# Qwiic_Ninja_Star.net
KiCad netlist of a schematic drawn in EAGLE
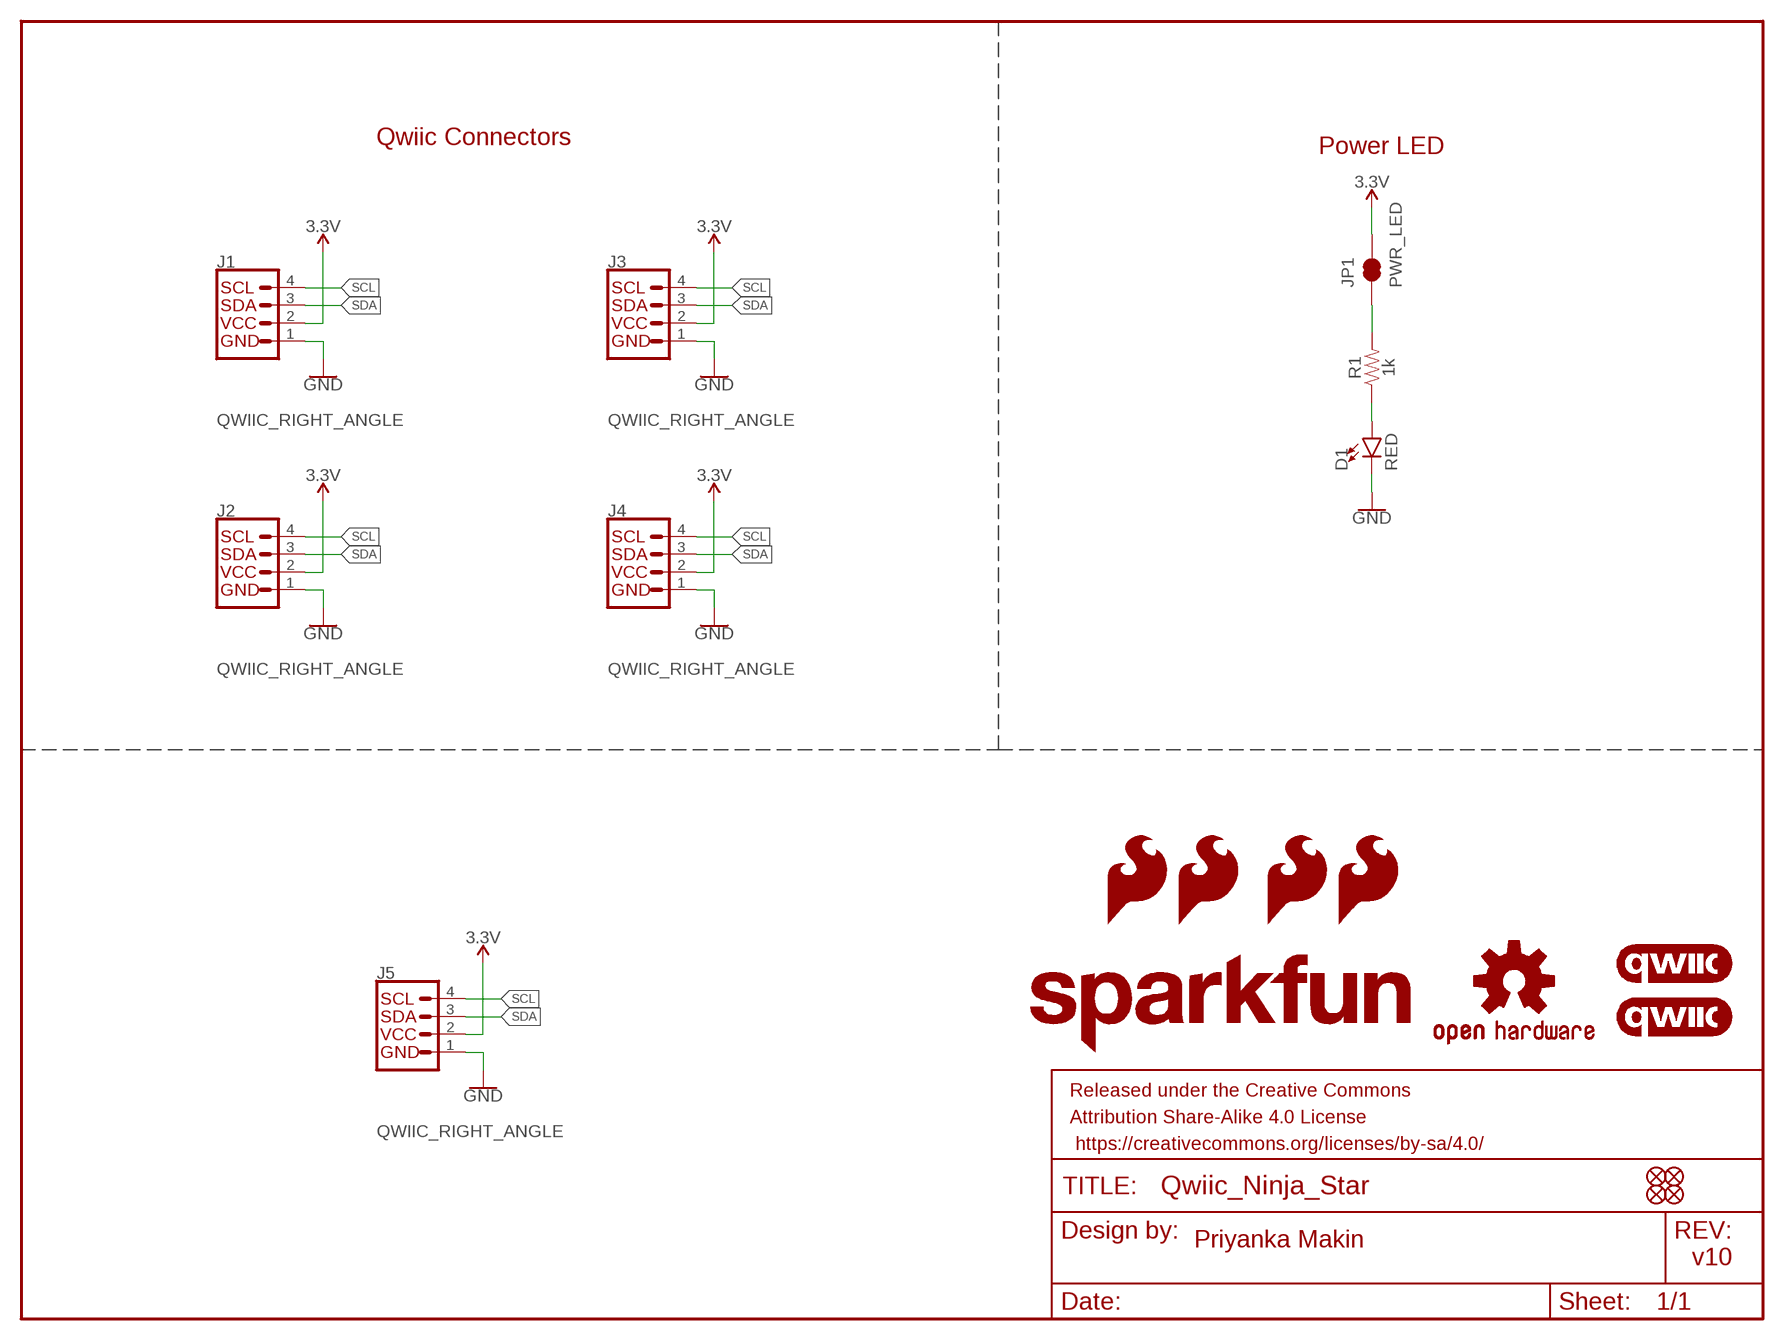
[diagram p0: schematic, sheet 1]

(export (version "E")
  (design (tool "Eeschema 10.0.6"))
  (components
    (comp (ref "D1")
      (value "RED")
      (footprint "eagle-import:LED-0603")
      (libsource (lib "eagle-import") (part "LED-RED0603"))
    )
    (comp (ref "FD1")
      (value "FIDUCIAL1X2")
      (footprint "eagle-import:FIDUCIAL-1X2")
      (libsource (lib "eagle-import") (part "FIDUCIAL1X2"))
    )
    (comp (ref "FD2")
      (value "FIDUCIAL1X2")
      (footprint "eagle-import:FIDUCIAL-1X2")
      (libsource (lib "eagle-import") (part "FIDUCIAL1X2"))
    )
    (comp (ref "FD3")
      (value "FIDUCIAL1X2")
      (footprint "eagle-import:FIDUCIAL-1X2")
      (libsource (lib "eagle-import") (part "FIDUCIAL1X2"))
    )
    (comp (ref "FD4")
      (value "FIDUCIAL1X2")
      (footprint "eagle-import:FIDUCIAL-1X2")
      (libsource (lib "eagle-import") (part "FIDUCIAL1X2"))
    )
    (comp (ref "FRAME1")
      (value "FRAME-LETTER")
      (footprint "eagle-import:CREATIVE_COMMONS")
      (libsource (lib "eagle-import") (part "FRAME-LETTER"))
    )
    (comp (ref "J1")
      (value "QWIIC_RIGHT_ANGLE")
      (footprint "eagle-import:JST04_1MM_RA")
      (libsource (lib "eagle-import") (part "QWIIC_CONNECTORJS-1MM"))
    )
    (comp (ref "J2")
      (value "QWIIC_RIGHT_ANGLE")
      (footprint "eagle-import:JST04_1MM_RA")
      (libsource (lib "eagle-import") (part "QWIIC_CONNECTORJS-1MM"))
    )
    (comp (ref "J3")
      (value "QWIIC_RIGHT_ANGLE")
      (footprint "eagle-import:JST04_1MM_RA")
      (libsource (lib "eagle-import") (part "QWIIC_CONNECTORJS-1MM"))
    )
    (comp (ref "J4")
      (value "QWIIC_RIGHT_ANGLE")
      (footprint "eagle-import:JST04_1MM_RA")
      (libsource (lib "eagle-import") (part "QWIIC_CONNECTORJS-1MM"))
    )
    (comp (ref "J5")
      (value "QWIIC_RIGHT_ANGLE")
      (footprint "eagle-import:JST04_1MM_RA")
      (libsource (lib "eagle-import") (part "QWIIC_CONNECTORJS-1MM"))
    )
    (comp (ref "JP1")
      (value "PWR_LED")
      (footprint "eagle-import:SMT-JUMPER_2_NC_TRACE_SILK")
      (libsource (lib "eagle-import") (part "JUMPER-SMT_2_NC_TRACE_SILK"))
    )
    (comp (ref "LOGO1")
      (value "QWIIC_LOGO_5MM")
      (footprint "eagle-import:QWIIC_5MM")
      (libsource (lib "eagle-import") (part "QWIIC_LOGO_5MM"))
    )
    (comp (ref "LOGO2")
      (value "QWIIC_LOGO_5MM")
      (footprint "eagle-import:QWIIC_5MM")
      (libsource (lib "eagle-import") (part "QWIIC_LOGO_5MM"))
    )
    (comp (ref "LOGO3")
      (value "OSHW-LOGOS")
      (footprint "eagle-import:OSHW-LOGO-S")
      (libsource (lib "eagle-import") (part "OSHW-LOGOS"))
    )
    (comp (ref "LOGO4")
      (value "SFE_LOGO_NAME.2_INCH")
      (footprint "eagle-import:SFE_LOGO_NAME_.2")
      (libsource (lib "eagle-import") (part "SFE_LOGO_NAME.2_INCH"))
    )
    (comp (ref "LOGO5")
      (value "SFE_LOGO_FLAME.1_INCH")
      (footprint "eagle-import:SFE_LOGO_FLAME_.1")
      (libsource (lib "eagle-import") (part "SFE_LOGO_FLAME.1_INCH"))
    )
    (comp (ref "LOGO6")
      (value "SFE_LOGO_FLAME.1_INCH")
      (footprint "eagle-import:SFE_LOGO_FLAME_.1")
      (libsource (lib "eagle-import") (part "SFE_LOGO_FLAME.1_INCH"))
    )
    (comp (ref "LOGO7")
      (value "SFE_LOGO_FLAME.1_INCH")
      (footprint "eagle-import:SFE_LOGO_FLAME_.1")
      (libsource (lib "eagle-import") (part "SFE_LOGO_FLAME.1_INCH"))
    )
    (comp (ref "LOGO8")
      (value "SFE_LOGO_FLAME.1_INCH")
      (footprint "eagle-import:SFE_LOGO_FLAME_.1")
      (libsource (lib "eagle-import") (part "SFE_LOGO_FLAME.1_INCH"))
    )
    (comp (ref "R1")
      (value "1k")
      (footprint "eagle-import:0603")
      (libsource (lib "eagle-import") (part "1KOHM-0603-1/10W-1%"))
    )
  )
  (nets
    (net (code "1") (name "3.3V") (class "Default")
      (node (ref "J1") (pin "2") (pinfunction "2_2") (pintype "power_in"))
      (node (ref "J2") (pin "2") (pinfunction "2_2") (pintype "power_in"))
      (node (ref "J3") (pin "2") (pinfunction "2_2") (pintype "power_in"))
      (node (ref "J4") (pin "2") (pinfunction "2_2") (pintype "power_in"))
      (node (ref "J5") (pin "2") (pinfunction "2_2") (pintype "power_in"))
      (node (ref "JP1") (pin "2") (pinfunction "2_2") (pintype "passive"))
    )
    (net (code "2") (name "GND") (class "Default")
      (node (ref "D1") (pin "C") (pinfunction "C_C") (pintype "passive"))
      (node (ref "J1") (pin "1") (pinfunction "1_1") (pintype "power_in"))
      (node (ref "J2") (pin "1") (pinfunction "1_1") (pintype "power_in"))
      (node (ref "J3") (pin "1") (pinfunction "1_1") (pintype "power_in"))
      (node (ref "J4") (pin "1") (pinfunction "1_1") (pintype "power_in"))
      (node (ref "J5") (pin "1") (pinfunction "1_1") (pintype "power_in"))
    )
    (net (code "3") (name "Net-(D1-PadA)") (class "Default")
      (node (ref "D1") (pin "A") (pinfunction "A_A") (pintype "passive"))
      (node (ref "R1") (pin "1") (pinfunction "1_1") (pintype "passive"))
    )
    (net (code "4") (name "Net-(JP1-Pad1)") (class "Default")
      (node (ref "JP1") (pin "1") (pinfunction "1_1") (pintype "passive"))
      (node (ref "R1") (pin "2") (pinfunction "2_2") (pintype "passive"))
    )
    (net (code "5") (name "SCL") (class "Default")
      (node (ref "J1") (pin "4") (pinfunction "4_4") (pintype "passive"))
      (node (ref "J2") (pin "4") (pinfunction "4_4") (pintype "passive"))
      (node (ref "J3") (pin "4") (pinfunction "4_4") (pintype "passive"))
      (node (ref "J4") (pin "4") (pinfunction "4_4") (pintype "passive"))
      (node (ref "J5") (pin "4") (pinfunction "4_4") (pintype "passive"))
    )
    (net (code "6") (name "SDA") (class "Default")
      (node (ref "J1") (pin "3") (pinfunction "3_3") (pintype "passive"))
      (node (ref "J2") (pin "3") (pinfunction "3_3") (pintype "passive"))
      (node (ref "J3") (pin "3") (pinfunction "3_3") (pintype "passive"))
      (node (ref "J4") (pin "3") (pinfunction "3_3") (pintype "passive"))
      (node (ref "J5") (pin "3") (pinfunction "3_3") (pintype "passive"))
    )
  )
)
